# breakout.net
KiCad netlist of a schematic drawn in EAGLE
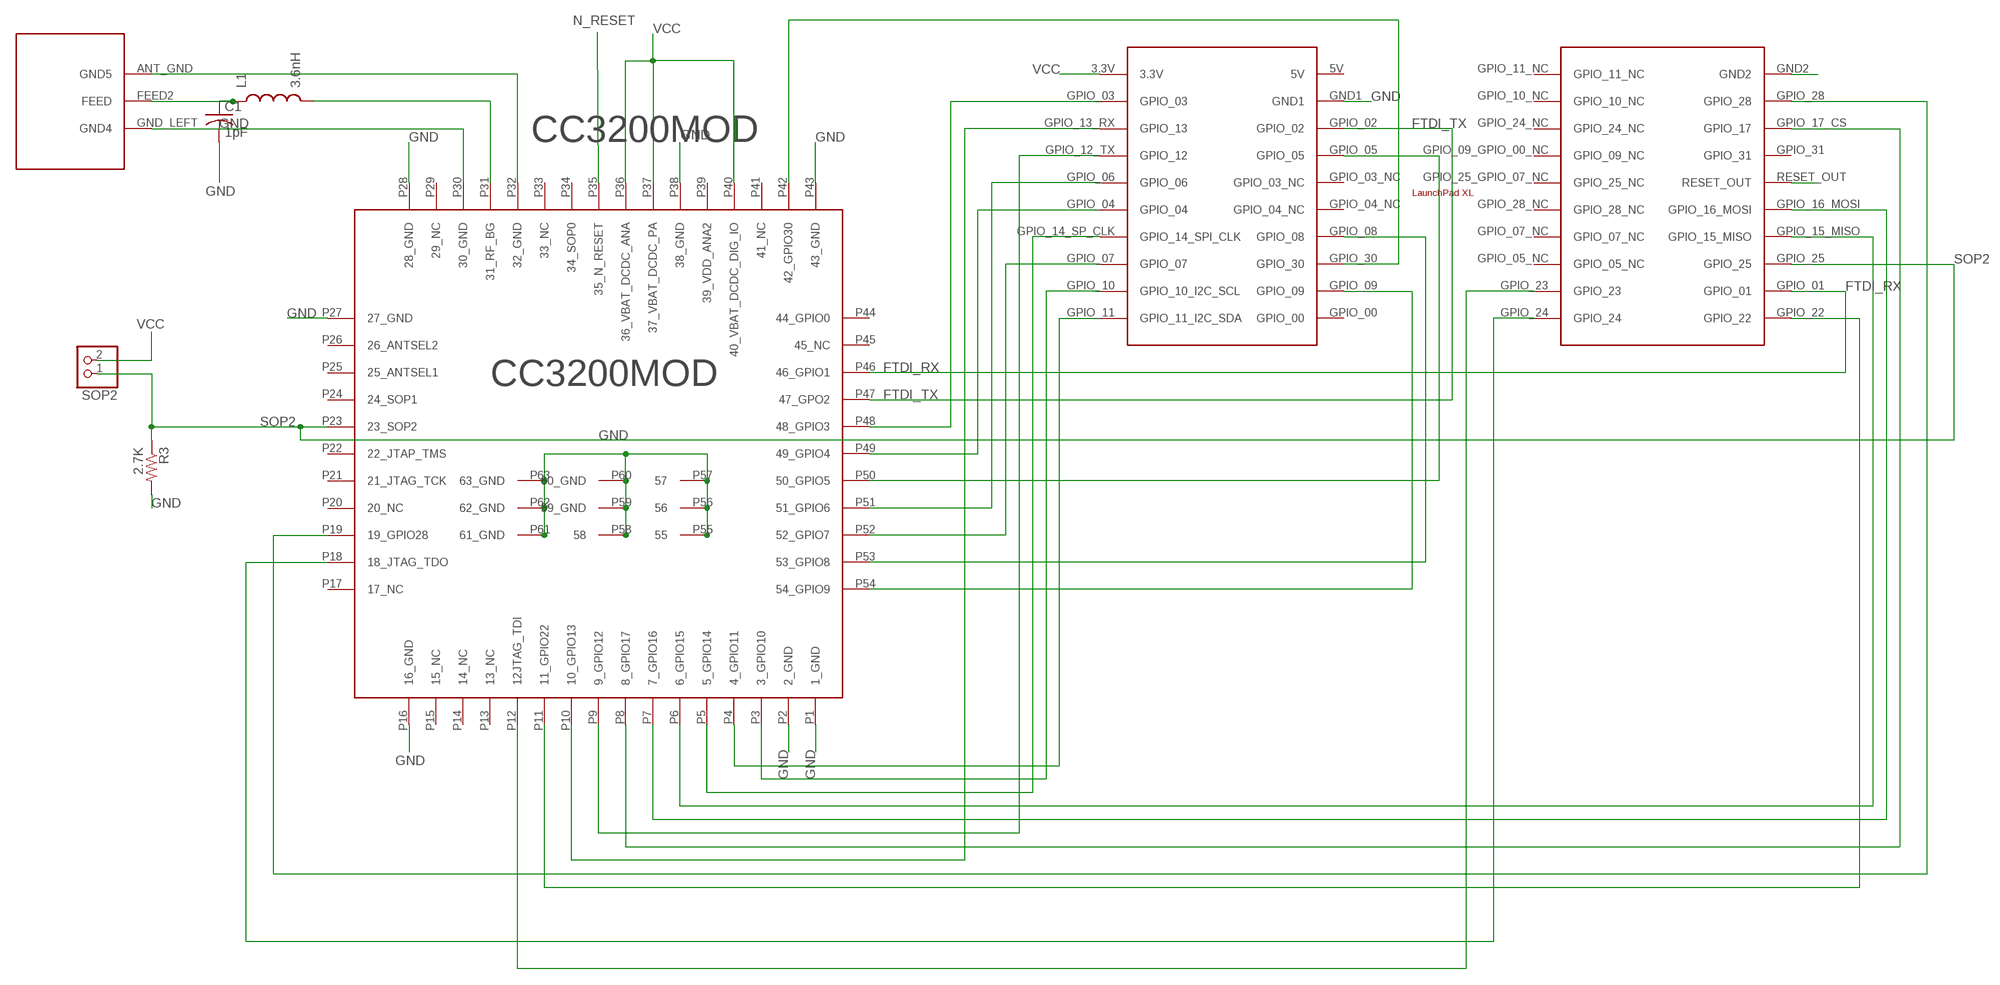
[diagram p0: schematic, sheet 1]
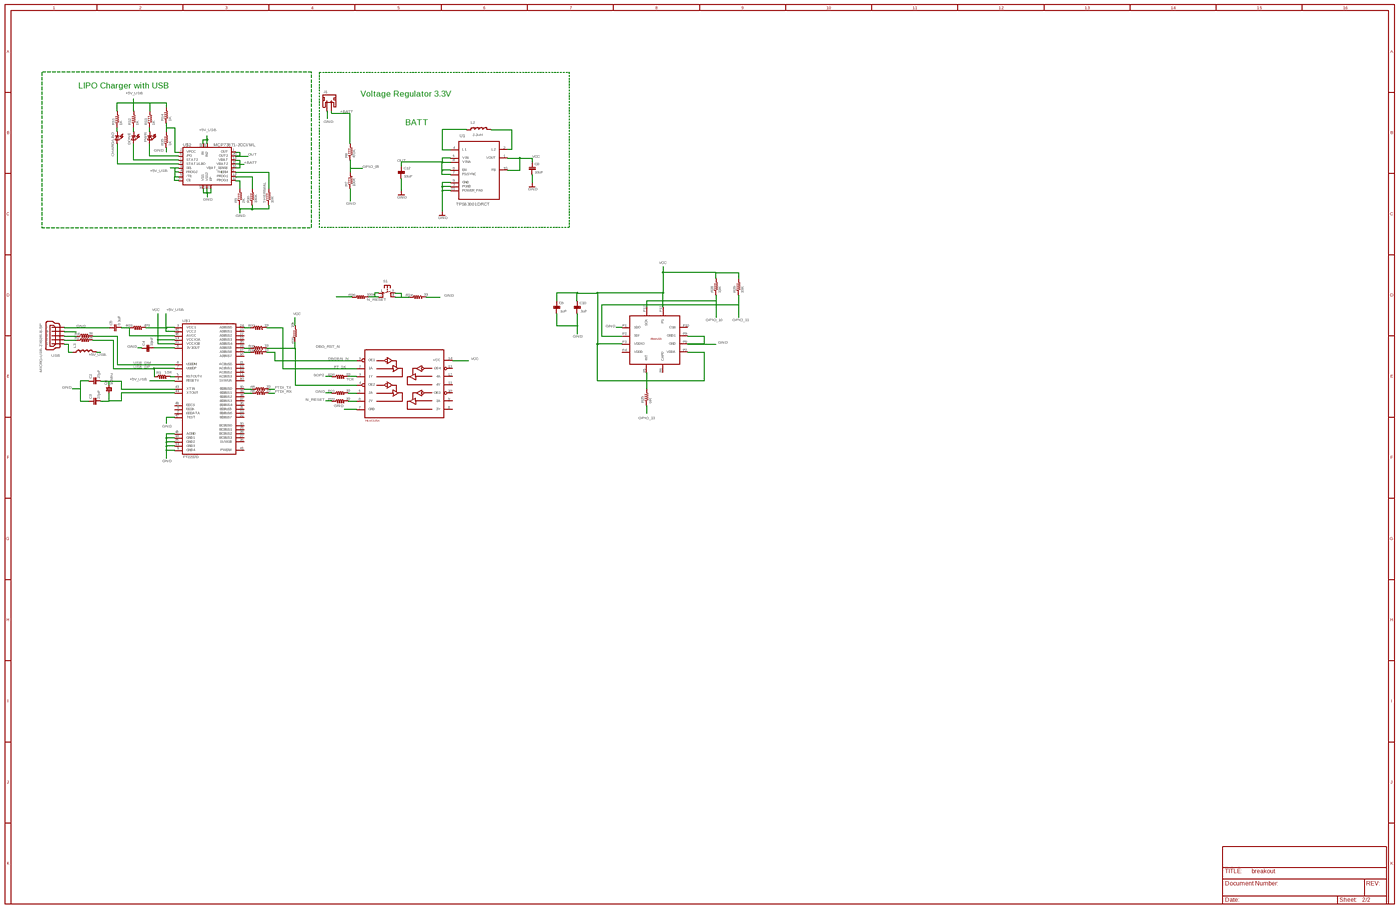
[diagram p1: schematic, sheet 2, overview]
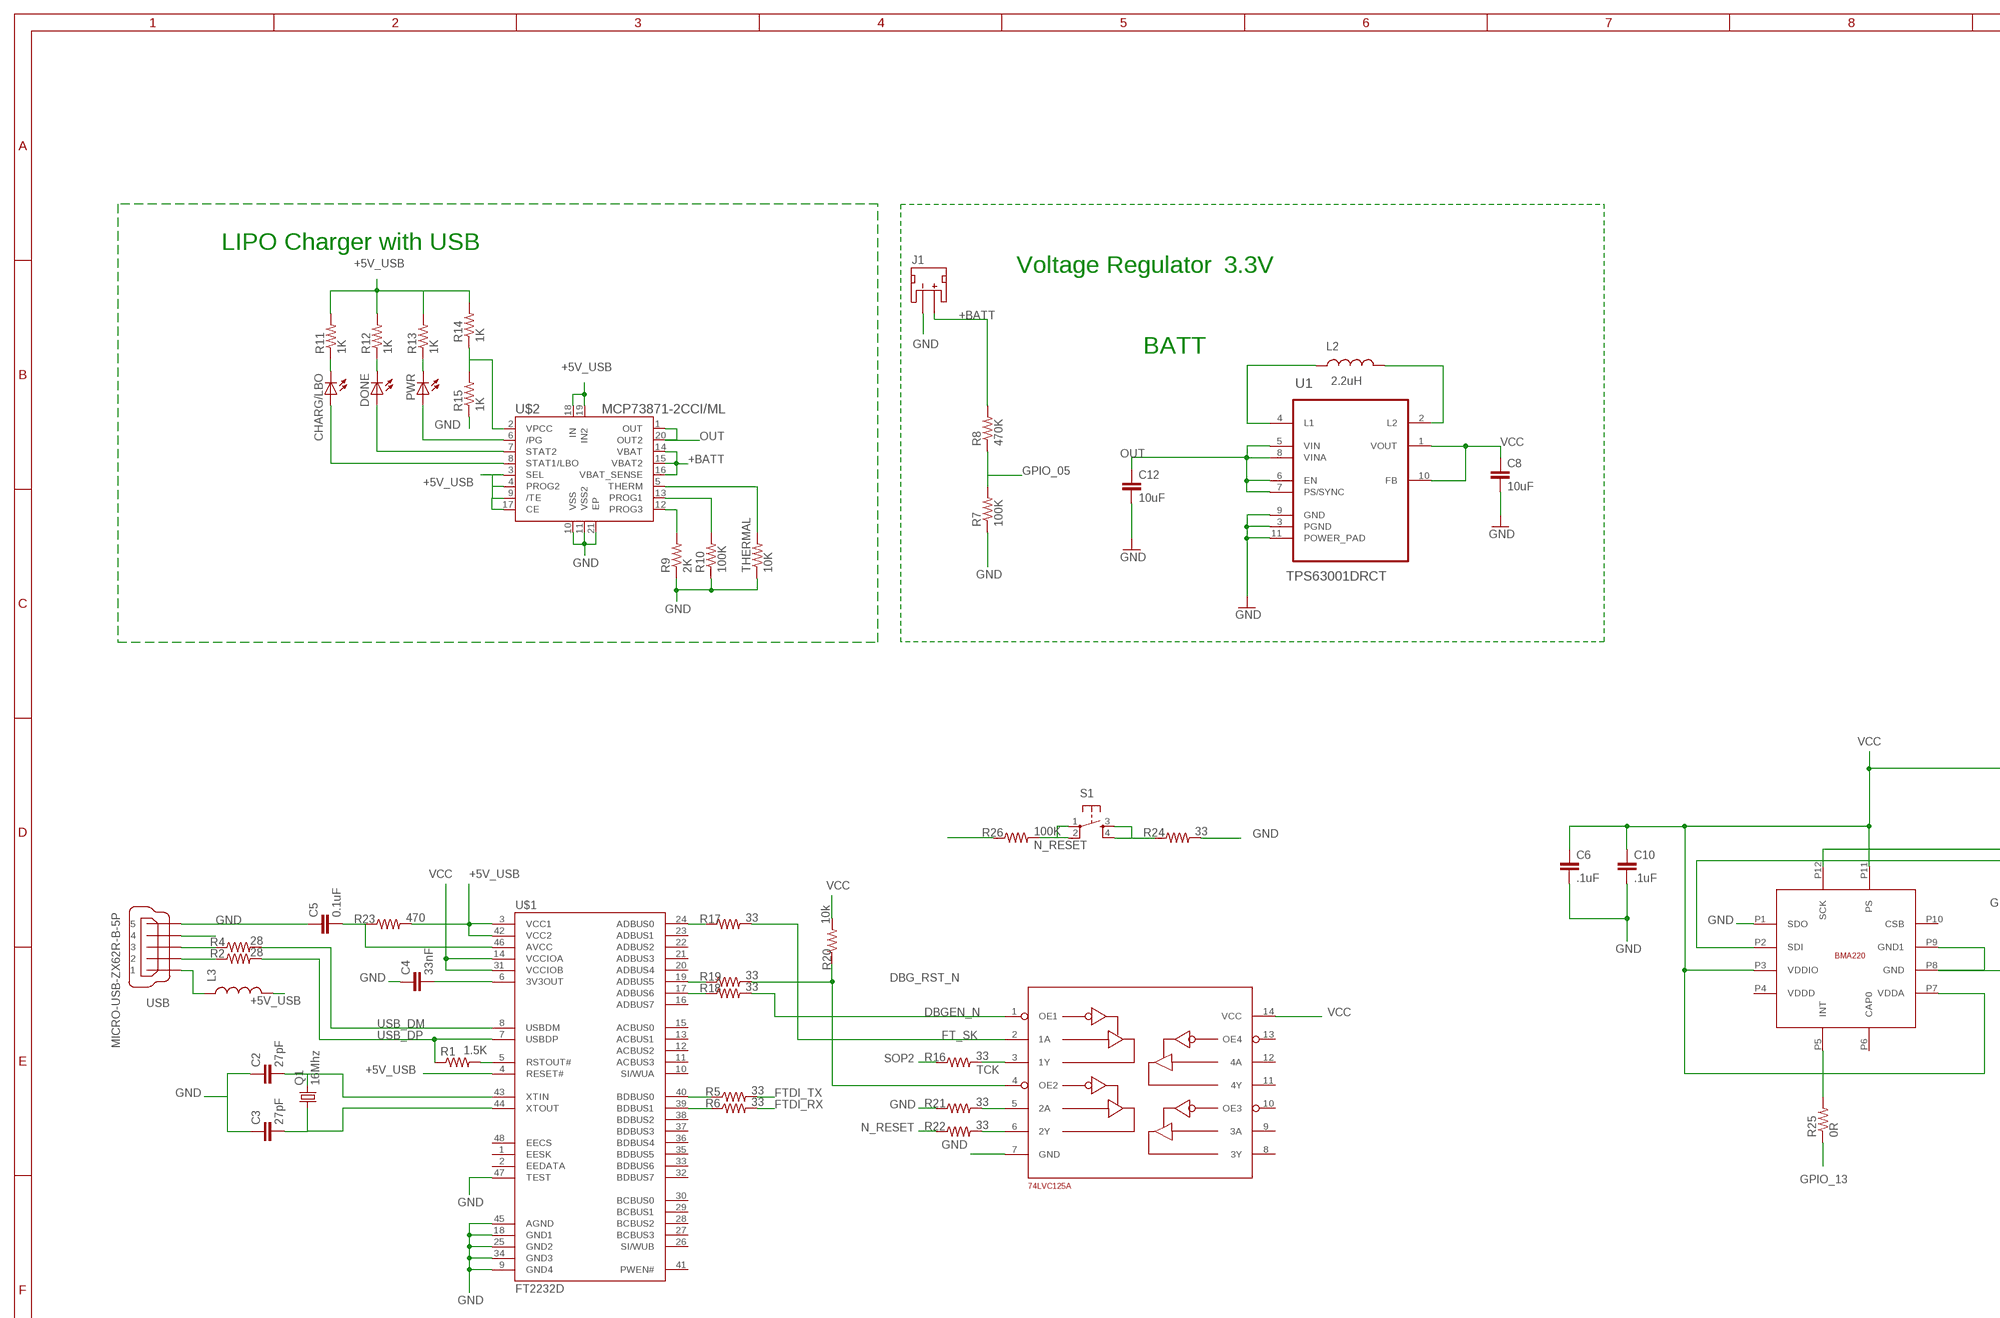
[diagram p2: schematic, sheet 2, part 1 of 4]
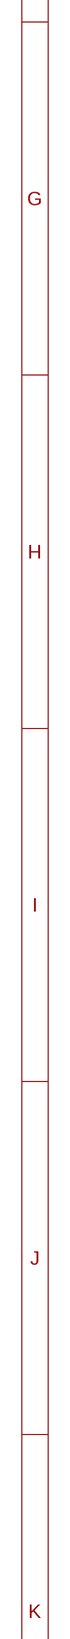
[diagram p3: schematic, sheet 2, part 2 of 4]
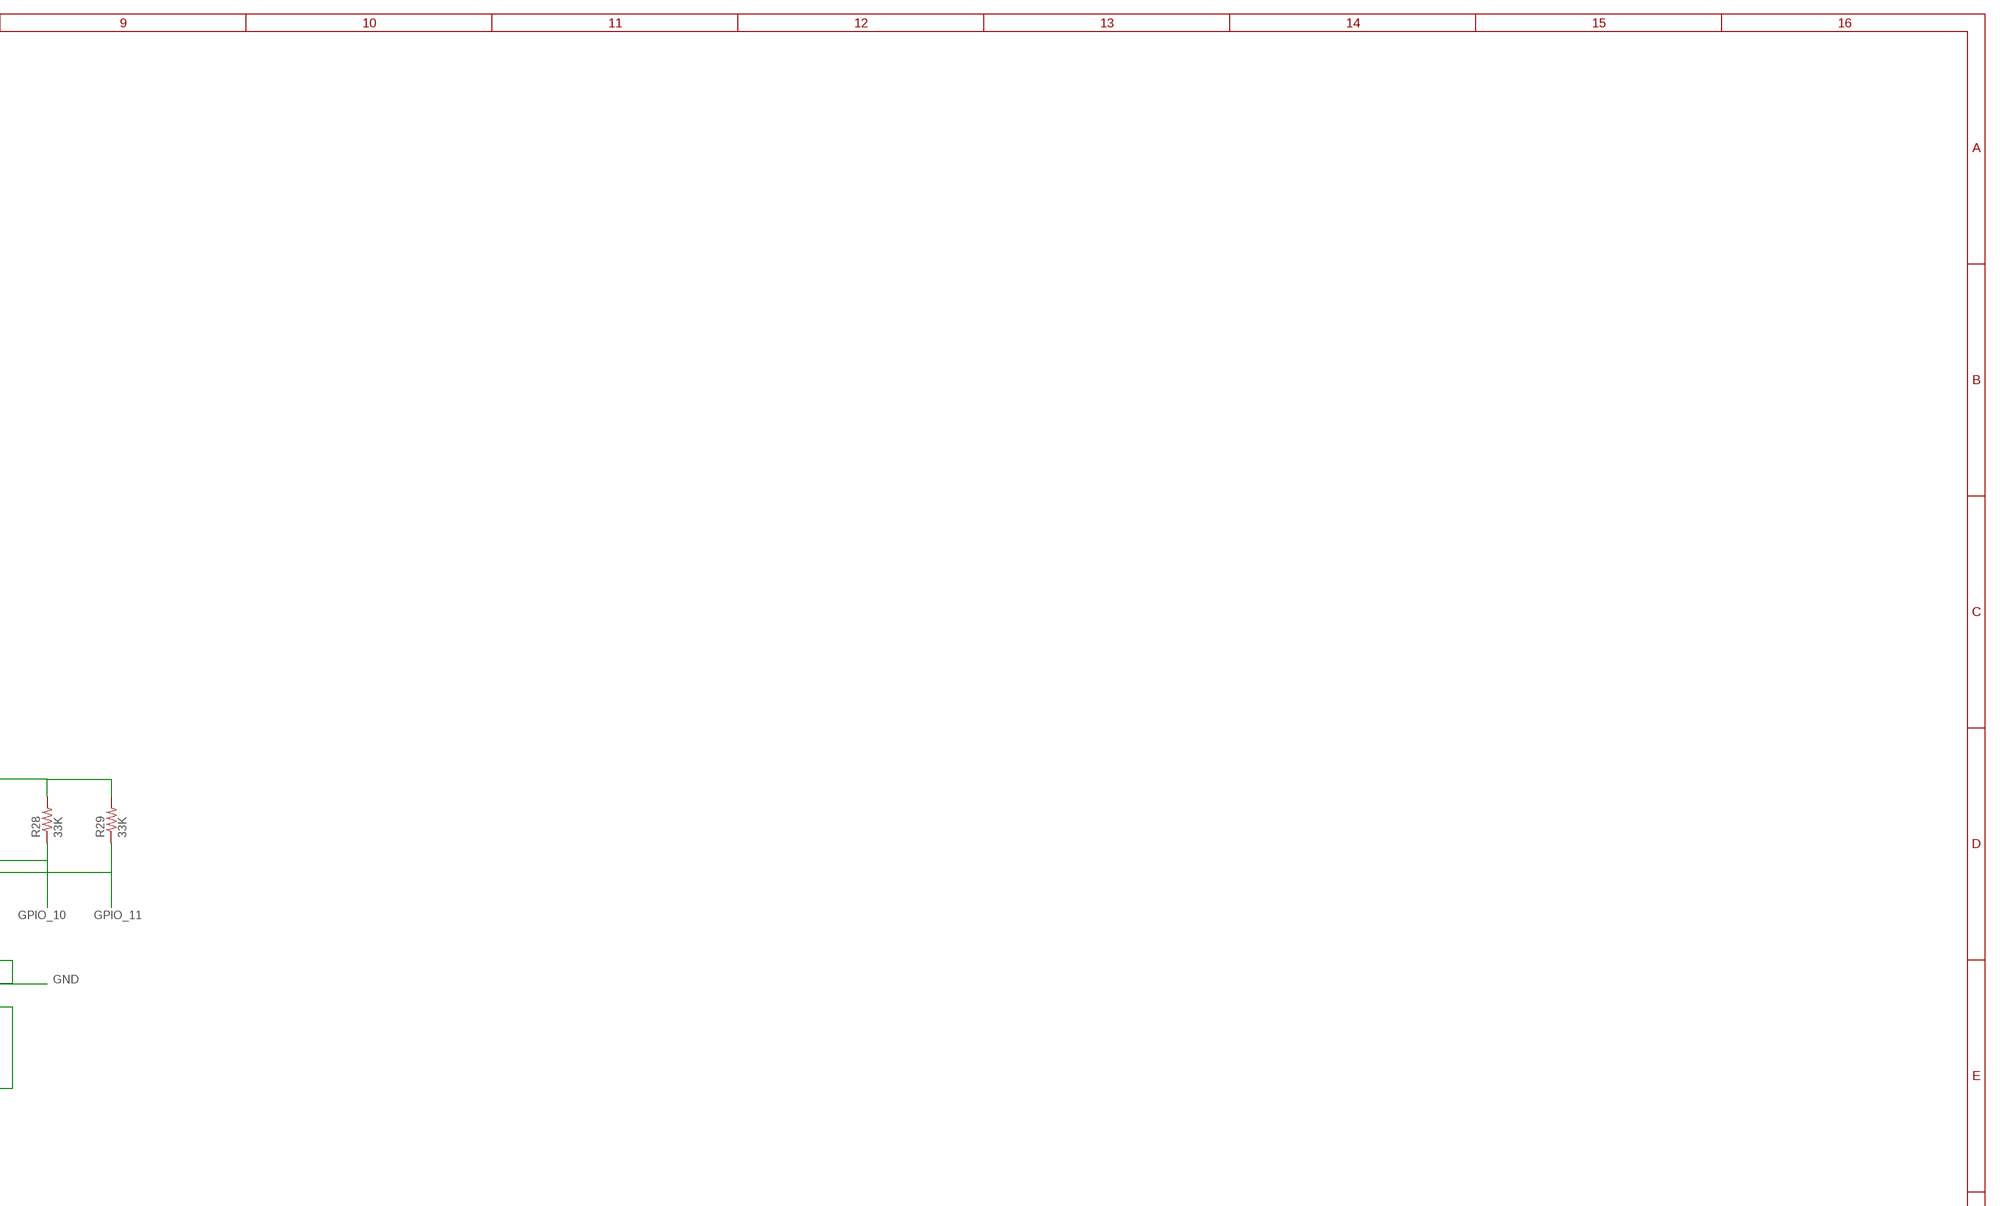
[diagram p4: schematic, sheet 2, part 3 of 4]
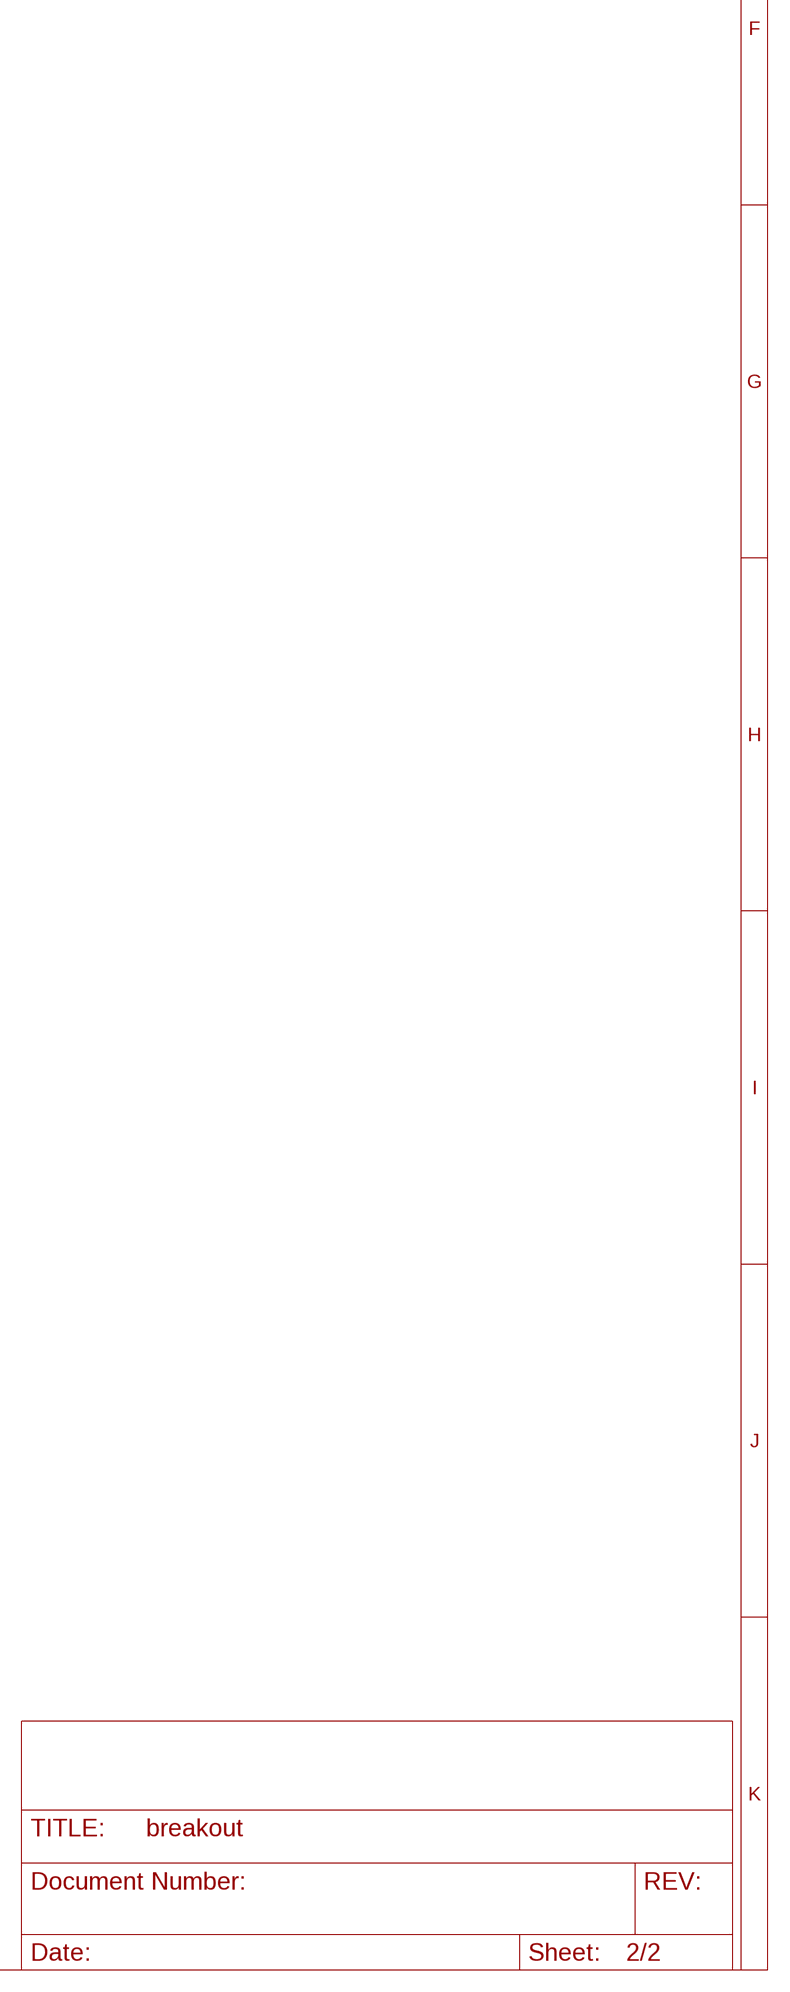
[diagram p5: schematic, sheet 2, part 4 of 4]

(export (version "E")
  (design (tool "Eeschema 10.0.6"))
  (components
    (comp (ref "C2")
      (value "27pF")
      (footprint "eagle-import:0402-CAP")
      (libsource (lib "eagle-import") (part "SparkFun-Passives_CAP0402-CAP"))
    )
    (comp (ref "C3")
      (value "27pF")
      (footprint "eagle-import:0402-CAP")
      (libsource (lib "eagle-import") (part "SparkFun-Passives_CAP0402-CAP"))
    )
    (comp (ref "C4")
      (value "33nF")
      (footprint "eagle-import:0402-CAP")
      (libsource (lib "eagle-import") (part "SparkFun-Passives_CAP0402-CAP"))
    )
    (comp (ref "C5")
      (value "0.1uF")
      (footprint "eagle-import:0402-CAP")
      (libsource (lib "eagle-import") (part "SparkFun-Passives_CAP0402-CAP"))
    )
    (comp (ref "C6")
      (value ".1uF")
      (footprint "eagle-import:0402-CAP")
      (libsource (lib "eagle-import") (part "CAP0402-CAP"))
    )
    (comp (ref "C8")
      (value "10uF")
      (footprint "eagle-import:C0603")
      (libsource (lib "eagle-import") (part "C-EUC0603"))
    )
    (comp (ref "C10")
      (value ".1uF")
      (footprint "eagle-import:0402-CAP")
      (libsource (lib "eagle-import") (part "CAP0402-CAP"))
    )
    (comp (ref "C12")
      (value "10uF")
      (footprint "eagle-import:C0603")
      (libsource (lib "eagle-import") (part "C-EUC0603"))
    )
    (comp (ref "CHARG/LBO")
      (value "LEDSML0603")
      (footprint "eagle-import:SML0603")
      (libsource (lib "eagle-import") (part "LEDSML0603"))
    )
    (comp (ref "DONE")
      (value "LEDSML0603")
      (footprint "eagle-import:SML0603")
      (libsource (lib "eagle-import") (part "LEDSML0603"))
    )
    (comp (ref "J1")
      (value "JST_2MM_MALE")
      (footprint "eagle-import:JST-2-SMD")
      (libsource (lib "eagle-import") (part "JST_2MM_MALE"))
    )
    (comp (ref "L2")
      (value "2.2uH")
      (footprint "eagle-import:0805")
      (libsource (lib "eagle-import") (part "INDUCTOR0805"))
    )
    (comp (ref "L3")
      (value "INDUCTOR-SPARKFUN0603")
      (footprint "eagle-import:0603")
      (libsource (lib "eagle-import") (part "INDUCTOR-SPARKFUN0603"))
    )
    (comp (ref "PWR")
      (value "LEDSML0603")
      (footprint "eagle-import:SML0603")
      (libsource (lib "eagle-import") (part "LEDSML0603"))
    )
    (comp (ref "Q1")
      (value "16Mhz")
      (footprint "eagle-import:TC26H")
      (libsource (lib "eagle-import") (part "CRYSTALTC26H"))
    )
    (comp (ref "R1")
      (value "1.5K")
      (footprint "eagle-import:0603-RES")
      (libsource (lib "eagle-import") (part "RESISTOR0603"))
    )
    (comp (ref "R2")
      (value "28")
      (footprint "eagle-import:0603-RES")
      (libsource (lib "eagle-import") (part "RESISTOR0603-RES"))
    )
    (comp (ref "R4")
      (value "28")
      (footprint "eagle-import:0603-RES")
      (libsource (lib "eagle-import") (part "RESISTOR0603-RES"))
    )
    (comp (ref "R5")
      (value "33")
      (footprint "eagle-import:0603-RES")
      (libsource (lib "eagle-import") (part "RESISTOR0603"))
    )
    (comp (ref "R6")
      (value "33")
      (footprint "eagle-import:0603-RES")
      (libsource (lib "eagle-import") (part "RESISTOR0603"))
    )
    (comp (ref "R7")
      (value "100K")
      (footprint "eagle-import:0603-RES")
      (libsource (lib "eagle-import") (part "RESISTOR0603"))
    )
    (comp (ref "R8")
      (value "470K")
      (footprint "eagle-import:0603-RES")
      (libsource (lib "eagle-import") (part "RESISTOR0603"))
    )
    (comp (ref "R9")
      (value "2K")
      (footprint "eagle-import:0603-RES")
      (libsource (lib "eagle-import") (part "RESISTOR0603-RES"))
    )
    (comp (ref "R10")
      (value "100K")
      (footprint "eagle-import:0603-RES")
      (libsource (lib "eagle-import") (part "RESISTOR0603-RES"))
    )
    (comp (ref "R11")
      (value "1K")
      (footprint "eagle-import:0603-RES")
      (libsource (lib "eagle-import") (part "RESISTOR0603-RES"))
    )
    (comp (ref "R12")
      (value "1K")
      (footprint "eagle-import:0603-RES")
      (libsource (lib "eagle-import") (part "RESISTOR0603-RES"))
    )
    (comp (ref "R13")
      (value "1K")
      (footprint "eagle-import:0603-RES")
      (libsource (lib "eagle-import") (part "RESISTOR0603-RES"))
    )
    (comp (ref "R14")
      (value "1K")
      (footprint "eagle-import:0603-RES")
      (libsource (lib "eagle-import") (part "RESISTOR0603-RES"))
    )
    (comp (ref "R15")
      (value "1K")
      (footprint "eagle-import:0603-RES")
      (libsource (lib "eagle-import") (part "RESISTOR0603-RES"))
    )
    (comp (ref "R16")
      (value "33")
      (footprint "eagle-import:0603-RES")
      (libsource (lib "eagle-import") (part "RESISTOR0603"))
    )
    (comp (ref "R17")
      (value "33")
      (footprint "eagle-import:0603-RES")
      (libsource (lib "eagle-import") (part "RESISTOR0603"))
    )
    (comp (ref "R18")
      (value "33")
      (footprint "eagle-import:0603-RES")
      (libsource (lib "eagle-import") (part "RESISTOR0603"))
    )
    (comp (ref "R19")
      (value "33")
      (footprint "eagle-import:0603-RES")
      (libsource (lib "eagle-import") (part "RESISTOR0603"))
    )
    (comp (ref "R20")
      (value "10k")
      (footprint "eagle-import:0603-RES")
      (libsource (lib "eagle-import") (part "RESISTOR0603"))
    )
    (comp (ref "R21")
      (value "33")
      (footprint "eagle-import:0603-RES")
      (libsource (lib "eagle-import") (part "RESISTOR0603"))
    )
    (comp (ref "R22")
      (value "33")
      (footprint "eagle-import:0603-RES")
      (libsource (lib "eagle-import") (part "RESISTOR0603"))
    )
    (comp (ref "R23")
      (value "470")
      (footprint "eagle-import:0603-RES")
      (libsource (lib "eagle-import") (part "RESISTOR0603"))
    )
    (comp (ref "R24")
      (value "33")
      (footprint "eagle-import:0603-RES")
      (libsource (lib "eagle-import") (part "RESISTOR0603"))
    )
    (comp (ref "R25")
      (value "0R")
      (footprint "eagle-import:0603-RES")
      (libsource (lib "eagle-import") (part "RESISTOR0603-RES"))
    )
    (comp (ref "R26")
      (value "100K")
      (footprint "eagle-import:0603-RES")
      (libsource (lib "eagle-import") (part "RESISTOR0603"))
    )
    (comp (ref "R28")
      (value "33K")
      (footprint "eagle-import:0402-RES")
      (libsource (lib "eagle-import") (part "RESISTOR0402-RES"))
    )
    (comp (ref "R29")
      (value "33K")
      (footprint "eagle-import:0402-RES")
      (libsource (lib "eagle-import") (part "RESISTOR0402-RES"))
    )
    (comp (ref "S1")
      (value "TAC_SWITCHSMD")
      (footprint "eagle-import:TACTILE_SWITCH_SMD")
      (libsource (lib "eagle-import") (part "TAC_SWITCHSMD"))
    )
    (comp (ref "THERMAL")
      (value "10K")
      (footprint "eagle-import:0603-RES")
      (libsource (lib "eagle-import") (part "RESISTOR0603-RES"))
    )
    (comp (ref "U$1")
      (value "FT2232D")
      (footprint "eagle-import:LQFP-48")
      (libsource (lib "eagle-import") (part "FT2232D"))
    )
    (comp (ref "U$2")
      (value "MCP73871-2CCI/ML")
      (footprint "eagle-import:QFN20-4X4")
      (libsource (lib "eagle-import") (part "MCP73871ML-2CCI/"))
    )
    (comp (ref "U$3")
      (value "DECADE-74LVC125A")
      (footprint "eagle-import:DECADE-SO-14")
      (libsource (lib "eagle-import") (part "DECADE-74LVC125A"))
    )
    (comp (ref "U$4")
      (value "BMA220")
      (footprint "eagle-import:BMA222")
      (libsource (lib "eagle-import") (part "BMA220"))
    )
    (comp (ref "U1")
      (value "TPS63001DRCT")
      (footprint "eagle-import:SON50P300X300X100-11N")
      (libsource (lib "eagle-import") (part "TPS63001DRCT"))
    )
    (comp (ref "USB")
      (value "MICRO-USB-ZX62R-B-5P")
      (footprint "eagle-import:ZX62R-B-5P")
      (libsource (lib "eagle-import") (part "MICRO-USB-ZX62R-B-5P"))
    )
    (comp (ref "ANT_PAD")
      (value "ANT")
      (footprint "eagle-import:ANT")
      (libsource (lib "eagle-import") (part "ANT"))
    )
    (comp (ref "C1")
      (value "1pF")
      (footprint "eagle-import:C0402")
      (libsource (lib "eagle-import") (part "C-USC0402"))
    )
    (comp (ref "CC3200MOD")
      (value "CC3200")
      (footprint "eagle-import:CC3200MOD")
      (libsource (lib "eagle-import") (part "CC3200"))
    )
    (comp (ref "L1")
      (value "3.6nH")
      (footprint "eagle-import:C0402")
      (libsource (lib "eagle-import") (part "INDUCTOR-SPARKFUN0402"))
    )
    (comp (ref "R3")
      (value "2.7K")
      (footprint "eagle-import:0603-RES")
      (libsource (lib "eagle-import") (part "RESISTOR0603"))
    )
    (comp (ref "SOP2")
      (value "PINHD-1X2")
      (footprint "eagle-import:1X02")
      (libsource (lib "eagle-import") (part "PINHD-1X2"))
    )
    (comp (ref "U11")
      (value "XL")
      (footprint "eagle-import:LAUNCHPADXL")
      (libsource (lib "eagle-import") (part "XL"))
    )
  )
  (nets
    (net (code "1") (name "+5V_USB") (class "Default")
      (node (ref "L3") (pin "2") (pinfunction "2_2") (pintype "passive"))
      (node (ref "R11") (pin "2") (pinfunction "2_2") (pintype "passive"))
      (node (ref "R12") (pin "2") (pinfunction "2_2") (pintype "passive"))
      (node (ref "R13") (pin "2") (pinfunction "2_2") (pintype "passive"))
      (node (ref "R14") (pin "2") (pinfunction "2_2") (pintype "passive"))
      (node (ref "R23") (pin "2") (pinfunction "2_2") (pintype "passive"))
      (node (ref "U$1") (pin "3") (pinfunction "VCC1_3") (pintype "power_in"))
      (node (ref "U$1") (pin "4") (pinfunction "RESET#_4") (pintype "bidirectional"))
      (node (ref "U$1") (pin "42") (pinfunction "VCC2_42") (pintype "power_in"))
      (node (ref "U$2") (pin "17") (pinfunction "CE_17") (pintype "input"))
      (node (ref "U$2") (pin "18") (pinfunction "IN_18") (pintype "power_in"))
      (node (ref "U$2") (pin "19") (pinfunction "IN2_19") (pintype "power_in"))
      (node (ref "U$2") (pin "3") (pinfunction "SEL_3") (pintype "input"))
      (node (ref "U$2") (pin "4") (pinfunction "PROG2_4") (pintype "input"))
      (node (ref "U$2") (pin "9") (pinfunction "/TE_9") (pintype "input"))
    )
    (net (code "2") (name "+BATT") (class "Default")
      (node (ref "J1") (pin "2") (pinfunction "+_2") (pintype "bidirectional"))
      (node (ref "R8") (pin "2") (pinfunction "2_2") (pintype "passive"))
      (node (ref "U$2") (pin "14") (pinfunction "VBAT_14") (pintype "bidirectional"))
      (node (ref "U$2") (pin "15") (pinfunction "VBAT2_15") (pintype "bidirectional"))
      (node (ref "U$2") (pin "16") (pinfunction "VBAT_SENSE_16") (pintype "bidirectional"))
    )
    (net (code "3") (name "DBGEN_N") (class "Default")
      (node (ref "R18") (pin "2") (pinfunction "2_2") (pintype "passive"))
      (node (ref "U$3") (pin "1") (pinfunction "OE1_1") (pintype "bidirectional"))
    )
    (net (code "4") (name "DBG_RST_N") (class "Default")
      (node (ref "R19") (pin "2") (pinfunction "2_2") (pintype "passive"))
      (node (ref "R20") (pin "1") (pinfunction "1_1") (pintype "passive"))
      (node (ref "U$3") (pin "4") (pinfunction "OE2_4") (pintype "bidirectional"))
    )
    (net (code "5") (name "FTDI_RX") (class "Default")
      (node (ref "CC3200MOD") (pin "P46") (pinfunction "46_GPIO1_P46") (pintype "bidirectional"))
      (node (ref "R6") (pin "2") (pinfunction "2_2") (pintype "passive"))
      (node (ref "U11") (pin "GPIO_01") (pinfunction "GPIO_01_GPIO_01") (pintype "bidirectional"))
    )
    (net (code "6") (name "FTDI_TX") (class "Default")
      (node (ref "CC3200MOD") (pin "P47") (pinfunction "47_GPO2_P47") (pintype "bidirectional"))
      (node (ref "R5") (pin "2") (pinfunction "2_2") (pintype "passive"))
      (node (ref "U11") (pin "GPIO_02") (pinfunction "GPIO_02_GPIO_02") (pintype "bidirectional"))
    )
    (net (code "7") (name "FT_SK") (class "Default")
      (node (ref "R17") (pin "2") (pinfunction "2_2") (pintype "passive"))
      (node (ref "U$3") (pin "2") (pinfunction "1A_2") (pintype "bidirectional"))
    )
    (net (code "8") (name "GND") (class "Default")
      (node (ref "ANT_PAD") (pin "ANT_GND") (pinfunction "GND5_ANT_GND") (pintype "bidirectional"))
      (node (ref "ANT_PAD") (pin "GND_LEFT") (pinfunction "GND4_GND_LEFT") (pintype "bidirectional"))
      (node (ref "C1") (pin "2") (pinfunction "2_2") (pintype "passive"))
      (node (ref "C10") (pin "2") (pinfunction "2_2") (pintype "passive"))
      (node (ref "C12") (pin "2") (pinfunction "2_2") (pintype "passive"))
      (node (ref "C2") (pin "1") (pinfunction "1_1") (pintype "passive"))
      (node (ref "C3") (pin "1") (pinfunction "1_1") (pintype "passive"))
      (node (ref "C4") (pin "1") (pinfunction "1_1") (pintype "passive"))
      (node (ref "C5") (pin "1") (pinfunction "1_1") (pintype "passive"))
      (node (ref "C6") (pin "2") (pinfunction "2_2") (pintype "passive"))
      (node (ref "C8") (pin "2") (pinfunction "2_2") (pintype "passive"))
      (node (ref "CC3200MOD") (pin "P1") (pinfunction "1_GND_P1") (pintype "bidirectional"))
      (node (ref "CC3200MOD") (pin "P16") (pinfunction "16_GND_P16") (pintype "bidirectional"))
      (node (ref "CC3200MOD") (pin "P2") (pinfunction "2_GND_P2") (pintype "bidirectional"))
      (node (ref "CC3200MOD") (pin "P27") (pinfunction "27_GND_P27") (pintype "bidirectional"))
      (node (ref "CC3200MOD") (pin "P28") (pinfunction "28_GND_P28") (pintype "bidirectional"))
      (node (ref "CC3200MOD") (pin "P30") (pinfunction "30_GND_P30") (pintype "bidirectional"))
      (node (ref "CC3200MOD") (pin "P32") (pinfunction "32_GND_P32") (pintype "bidirectional"))
      (node (ref "CC3200MOD") (pin "P38") (pinfunction "38_GND_P38") (pintype "bidirectional"))
      (node (ref "CC3200MOD") (pin "P43") (pinfunction "43_GND_P43") (pintype "bidirectional"))
      (node (ref "CC3200MOD") (pin "P55") (pinfunction "55_P55") (pintype "bidirectional"))
      (node (ref "CC3200MOD") (pin "P56") (pinfunction "56_P56") (pintype "bidirectional"))
      (node (ref "CC3200MOD") (pin "P57") (pinfunction "57_P57") (pintype "bidirectional"))
      (node (ref "CC3200MOD") (pin "P58") (pinfunction "58_P58") (pintype "bidirectional"))
      (node (ref "CC3200MOD") (pin "P59") (pinfunction "59_GND_P59") (pintype "bidirectional"))
      (node (ref "CC3200MOD") (pin "P60") (pinfunction "60_GND_P60") (pintype "bidirectional"))
      (node (ref "CC3200MOD") (pin "P61") (pinfunction "61_GND_P61") (pintype "bidirectional"))
      (node (ref "CC3200MOD") (pin "P62") (pinfunction "62_GND_P62") (pintype "bidirectional"))
      (node (ref "CC3200MOD") (pin "P63") (pinfunction "63_GND_P63") (pintype "bidirectional"))
      (node (ref "J1") (pin "1") (pinfunction "-_1") (pintype "bidirectional"))
      (node (ref "R10") (pin "1") (pinfunction "1_1") (pintype "passive"))
      (node (ref "R15") (pin "1") (pinfunction "1_1") (pintype "passive"))
      (node (ref "R21") (pin "1") (pinfunction "1_1") (pintype "passive"))
      (node (ref "R24") (pin "2") (pinfunction "2_2") (pintype "passive"))
      (node (ref "R3") (pin "2") (pinfunction "2_2") (pintype "passive"))
      (node (ref "R7") (pin "1") (pinfunction "1_1") (pintype "passive"))
      (node (ref "R9") (pin "1") (pinfunction "1_1") (pintype "passive"))
      (node (ref "THERMAL") (pin "1") (pinfunction "1_1") (pintype "passive"))
      (node (ref "U$1") (pin "18") (pinfunction "GND1_18") (pintype "power_in"))
      (node (ref "U$1") (pin "25") (pinfunction "GND2_25") (pintype "power_in"))
      (node (ref "U$1") (pin "34") (pinfunction "GND3_34") (pintype "power_in"))
      (node (ref "U$1") (pin "45") (pinfunction "AGND_45") (pintype "power_in"))
      (node (ref "U$1") (pin "47") (pinfunction "TEST_47") (pintype "input"))
      (node (ref "U$1") (pin "9") (pinfunction "GND4_9") (pintype "bidirectional"))
      (node (ref "U$2") (pin "10") (pinfunction "VSS_10") (pintype "power_in"))
      (node (ref "U$2") (pin "11") (pinfunction "VSS2_11") (pintype "power_in"))
      (node (ref "U$2") (pin "21") (pinfunction "EP_21") (pintype "power_in"))
      (node (ref "U$3") (pin "7") (pinfunction "GND_7") (pintype "bidirectional"))
      (node (ref "U$4") (pin "P1") (pinfunction "SDO_P1") (pintype "bidirectional"))
      (node (ref "U$4") (pin "P8") (pinfunction "GND_P8") (pintype "bidirectional"))
      (node (ref "U$4") (pin "P9") (pinfunction "GND1_P9") (pintype "bidirectional"))
      (node (ref "U1") (pin "11") (pinfunction "POWER_PAD_11") (pintype "passive"))
      (node (ref "U1") (pin "3") (pinfunction "PGND_3") (pintype "passive"))
      (node (ref "U1") (pin "9") (pinfunction "GND_9") (pintype "passive"))
      (node (ref "U11") (pin "GND1") (pinfunction "GND1_GND1") (pintype "bidirectional"))
      (node (ref "U11") (pin "GND2") (pinfunction "GND2_GND2") (pintype "bidirectional"))
      (node (ref "USB") (pin "5") (pinfunction "5_5") (pintype "input"))
    )
    (net (code "9") (name "GPIO_05") (class "Default")
      (node (ref "CC3200MOD") (pin "P50") (pinfunction "50_GPIO5_P50") (pintype "bidirectional"))
      (node (ref "R7") (pin "2") (pinfunction "2_2") (pintype "passive"))
      (node (ref "R8") (pin "1") (pinfunction "1_1") (pintype "passive"))
      (node (ref "U11") (pin "GPIO_05") (pinfunction "GPIO_05_GPIO_05") (pintype "bidirectional"))
    )
    (net (code "10") (name "GPIO_10") (class "Default")
      (node (ref "CC3200MOD") (pin "P3") (pinfunction "3_GPIO10_P3") (pintype "bidirectional"))
      (node (ref "R28") (pin "1") (pinfunction "1_1") (pintype "passive"))
      (node (ref "U$4") (pin "P12") (pinfunction "SCK_P12") (pintype "bidirectional"))
      (node (ref "U11") (pin "GPIO_10") (pinfunction "GPIO_10_I2C_SCL_GPIO_10") (pintype "bidirectional"))
    )
    (net (code "11") (name "GPIO_11") (class "Default")
      (node (ref "CC3200MOD") (pin "P4") (pinfunction "4_GPIO11_P4") (pintype "bidirectional"))
      (node (ref "R29") (pin "1") (pinfunction "1_1") (pintype "passive"))
      (node (ref "U$4") (pin "P2") (pinfunction "SDI_P2") (pintype "bidirectional"))
      (node (ref "U11") (pin "GPIO_11") (pinfunction "GPIO_11_I2C_SDA_GPIO_11") (pintype "bidirectional"))
    )
    (net (code "12") (name "GPIO_13") (class "Default")
      (node (ref "CC3200MOD") (pin "P10") (pinfunction "10_GPIO13_P10") (pintype "bidirectional"))
      (node (ref "R25") (pin "1") (pinfunction "1_1") (pintype "passive"))
      (node (ref "U11") (pin "GPIO_13_RX") (pinfunction "GPIO_13_GPIO_13_RX") (pintype "bidirectional"))
    )
    (net (code "13") (name "N_RESET") (class "Default")
      (node (ref "CC3200MOD") (pin "P35") (pinfunction "35_N_RESET_P35") (pintype "bidirectional"))
      (node (ref "R22") (pin "1") (pinfunction "1_1") (pintype "passive"))
      (node (ref "R26") (pin "2") (pinfunction "2_2") (pintype "passive"))
      (node (ref "S1") (pin "1") (pinfunction "1_1") (pintype "passive"))
      (node (ref "S1") (pin "2") (pinfunction "2_2") (pintype "passive"))
      (node (ref "U11") (pin "RESET_OUT") (pinfunction "RESET_OUT_RESET_OUT") (pintype "bidirectional"))
    )
    (net (code "14") (name "Net-(ANT_PAD-FEED)") (class "Default")
      (node (ref "ANT_PAD") (pin "FEED2") (pinfunction "FEED_FEED2") (pintype "bidirectional"))
      (node (ref "C1") (pin "1") (pinfunction "1_1") (pintype "passive"))
      (node (ref "L1") (pin "1") (pinfunction "1_1") (pintype "passive"))
    )
    (net (code "15") (name "Net-(CC3200MOD-5_GPIO14)") (class "Default")
      (node (ref "CC3200MOD") (pin "P5") (pinfunction "5_GPIO14_P5") (pintype "bidirectional"))
      (node (ref "U11") (pin "GPIO_14_SP_CLK") (pinfunction "GPIO_14_SPI_CLK_GPIO_14_SP_CLK") (pintype "bidirectional"))
    )
    (net (code "16") (name "Net-(CC3200MOD-6_GPIO15)") (class "Default")
      (node (ref "CC3200MOD") (pin "P6") (pinfunction "6_GPIO15_P6") (pintype "bidirectional"))
      (node (ref "U11") (pin "GPIO_15_MISO") (pinfunction "GPIO_15_MISO_GPIO_15_MISO") (pintype "bidirectional"))
    )
    (net (code "17") (name "Net-(CC3200MOD-7_GPIO16)") (class "Default")
      (node (ref "CC3200MOD") (pin "P7") (pinfunction "7_GPIO16_P7") (pintype "bidirectional"))
      (node (ref "U11") (pin "GPIO_16_MOSI") (pinfunction "GPIO_16_MOSI_GPIO_16_MOSI") (pintype "bidirectional"))
    )
    (net (code "18") (name "Net-(CC3200MOD-8_GPIO17)") (class "Default")
      (node (ref "CC3200MOD") (pin "P8") (pinfunction "8_GPIO17_P8") (pintype "bidirectional"))
      (node (ref "U11") (pin "GPIO_17_CS") (pinfunction "GPIO_17_GPIO_17_CS") (pintype "bidirectional"))
    )
    (net (code "19") (name "Net-(CC3200MOD-9_GPIO12)") (class "Default")
      (node (ref "CC3200MOD") (pin "P9") (pinfunction "9_GPIO12_P9") (pintype "bidirectional"))
      (node (ref "U11") (pin "GPIO_12_TX") (pinfunction "GPIO_12_GPIO_12_TX") (pintype "bidirectional"))
    )
    (net (code "20") (name "Net-(CC3200MOD-11_GPIO22)") (class "Default")
      (node (ref "CC3200MOD") (pin "P11") (pinfunction "11_GPIO22_P11") (pintype "bidirectional"))
      (node (ref "U11") (pin "GPIO_22") (pinfunction "GPIO_22_GPIO_22") (pintype "bidirectional"))
    )
    (net (code "21") (name "Net-(CC3200MOD-12JTAG_TDI)") (class "Default")
      (node (ref "CC3200MOD") (pin "P12") (pinfunction "12JTAG_TDI_P12") (pintype "bidirectional"))
      (node (ref "U11") (pin "GPIO_23") (pinfunction "GPIO_23_GPIO_23") (pintype "bidirectional"))
    )
    (net (code "22") (name "Net-(CC3200MOD-18_JTAG_TDO)") (class "Default")
      (node (ref "CC3200MOD") (pin "P18") (pinfunction "18_JTAG_TDO_P18") (pintype "bidirectional"))
      (node (ref "U11") (pin "GPIO_24") (pinfunction "GPIO_24_GPIO_24") (pintype "bidirectional"))
    )
    (net (code "23") (name "Net-(CC3200MOD-19_GPIO28)") (class "Default")
      (node (ref "CC3200MOD") (pin "P19") (pinfunction "19_GPIO28_P19") (pintype "bidirectional"))
      (node (ref "U11") (pin "GPIO_28") (pinfunction "GPIO_28_GPIO_28") (pintype "bidirectional"))
    )
    (net (code "24") (name "Net-(CC3200MOD-31_RF_BG)") (class "Default")
      (node (ref "CC3200MOD") (pin "P31") (pinfunction "31_RF_BG_P31") (pintype "bidirectional"))
      (node (ref "L1") (pin "2") (pinfunction "2_2") (pintype "passive"))
    )
    (net (code "25") (name "Net-(CC3200MOD-42_GPIO30)") (class "Default")
      (node (ref "CC3200MOD") (pin "P42") (pinfunction "42_GPIO30_P42") (pintype "bidirectional"))
      (node (ref "U11") (pin "GPIO_30") (pinfunction "GPIO_30_GPIO_30") (pintype "bidirectional"))
    )
    (net (code "26") (name "Net-(CC3200MOD-48_GPIO3)") (class "Default")
      (node (ref "CC3200MOD") (pin "P48") (pinfunction "48_GPIO3_P48") (pintype "bidirectional"))
      (node (ref "U11") (pin "GPIO_03") (pinfunction "GPIO_03_GPIO_03") (pintype "bidirectional"))
    )
    (net (code "27") (name "Net-(CC3200MOD-49_GPIO4)") (class "Default")
      (node (ref "CC3200MOD") (pin "P49") (pinfunction "49_GPIO4_P49") (pintype "bidirectional"))
      (node (ref "U11") (pin "GPIO_04") (pinfunction "GPIO_04_GPIO_04") (pintype "bidirectional"))
    )
    (net (code "28") (name "Net-(CC3200MOD-51_GPIO6)") (class "Default")
      (node (ref "CC3200MOD") (pin "P51") (pinfunction "51_GPIO6_P51") (pintype "bidirectional"))
      (node (ref "U11") (pin "GPIO_06") (pinfunction "GPIO_06_GPIO_06") (pintype "bidirectional"))
    )
    (net (code "29") (name "Net-(CC3200MOD-52_GPIO7)") (class "Default")
      (node (ref "CC3200MOD") (pin "P52") (pinfunction "52_GPIO7_P52") (pintype "bidirectional"))
      (node (ref "U11") (pin "GPIO_07") (pinfunction "GPIO_07_GPIO_07") (pintype "bidirectional"))
    )
    (net (code "30") (name "Net-(CC3200MOD-53_GPIO8)") (class "Default")
      (node (ref "CC3200MOD") (pin "P53") (pinfunction "53_GPIO8_P53") (pintype "bidirectional"))
      (node (ref "U11") (pin "GPIO_08") (pinfunction "GPIO_08_GPIO_08") (pintype "bidirectional"))
    )
    (net (code "31") (name "Net-(CC3200MOD-54_GPIO9)") (class "Default")
      (node (ref "CC3200MOD") (pin "P54") (pinfunction "54_GPIO9_P54") (pintype "bidirectional"))
      (node (ref "U11") (pin "GPIO_09") (pinfunction "GPIO_09_GPIO_09") (pintype "bidirectional"))
    )
    (net (code "32") (name "Net-(CHARG/LBO-PadC)") (class "Default")
      (node (ref "CHARG/LBO") (pin "C") (pinfunction "C_C") (pintype "passive"))
      (node (ref "R11") (pin "1") (pinfunction "1_1") (pintype "passive"))
    )
    (net (code "33") (name "Net-(DONE-PadC)") (class "Default")
      (node (ref "DONE") (pin "C") (pinfunction "C_C") (pintype "passive"))
      (node (ref "R12") (pin "1") (pinfunction "1_1") (pintype "passive"))
    )
    (net (code "34") (name "Net-(L3-Pad1)") (class "Default")
      (node (ref "L3") (pin "1") (pinfunction "1_1") (pintype "passive"))
      (node (ref "USB") (pin "1") (pinfunction "1_1") (pintype "input"))
    )
    (net (code "35") (name "Net-(PWR-PadC)") (class "Default")
      (node (ref "PWR") (pin "C") (pinfunction "C_C") (pintype "passive"))
      (node (ref "R13") (pin "1") (pinfunction "1_1") (pintype "passive"))
    )
    (net (code "36") (name "Net-(R2-Pad1)") (class "Default")
      (node (ref "R2") (pin "1") (pinfunction "1_1") (pintype "passive"))
      (node (ref "USB") (pin "2") (pinfunction "2_2") (pintype "input"))
    )
    (net (code "37") (name "Net-(R4-Pad1)") (class "Default")
      (node (ref "R4") (pin "1") (pinfunction "1_1") (pintype "passive"))
      (node (ref "USB") (pin "3") (pinfunction "3_3") (pintype "input"))
    )
    (net (code "38") (name "Net-(R24-Pad1)") (class "Default")
      (node (ref "R24") (pin "1") (pinfunction "1_1") (pintype "passive"))
      (node (ref "S1") (pin "3") (pinfunction "3_3") (pintype "passive"))
      (node (ref "S1") (pin "4") (pinfunction "4_4") (pintype "passive"))
    )
    (net (code "39") (name "Net-(U$1-3V3OUT)") (class "Default")
      (node (ref "C4") (pin "2") (pinfunction "2_2") (pintype "passive"))
      (node (ref "U$1") (pin "6") (pinfunction "3V3OUT_6") (pintype "output"))
    )
    (net (code "40") (name "Net-(U$1-ADBUS0)") (class "Default")
      (node (ref "R17") (pin "1") (pinfunction "1_1") (pintype "passive"))
      (node (ref "U$1") (pin "24") (pinfunction "ADBUS0_24") (pintype "bidirectional"))
    )
    (net (code "41") (name "Net-(U$1-ADBUS5)") (class "Default")
      (node (ref "R19") (pin "1") (pinfunction "1_1") (pintype "passive"))
      (node (ref "U$1") (pin "19") (pinfunction "ADBUS5_19") (pintype "bidirectional"))
    )
    (net (code "42") (name "Net-(U$1-ADBUS6)") (class "Default")
      (node (ref "R18") (pin "1") (pinfunction "1_1") (pintype "passive"))
      (node (ref "U$1") (pin "17") (pinfunction "ADBUS6_17") (pintype "bidirectional"))
    )
    (net (code "43") (name "Net-(U$1-AVCC)") (class "Default")
      (node (ref "C5") (pin "2") (pinfunction "2_2") (pintype "passive"))
      (node (ref "R23") (pin "1") (pinfunction "1_1") (pintype "passive"))
      (node (ref "U$1") (pin "46") (pinfunction "AVCC_46") (pintype "bidirectional"))
    )
    (net (code "44") (name "Net-(U$1-BDBUS0)") (class "Default")
      (node (ref "R5") (pin "1") (pinfunction "1_1") (pintype "passive"))
      (node (ref "U$1") (pin "40") (pinfunction "BDBUS0_40") (pintype "output"))
    )
    (net (code "45") (name "Net-(U$1-BDBUS1)") (class "Default")
      (node (ref "R6") (pin "1") (pinfunction "1_1") (pintype "passive"))
      (node (ref "U$1") (pin "39") (pinfunction "BDBUS1_39") (pintype "input"))
    )
    (net (code "46") (name "Net-(U$1-RSTOUT#)") (class "Default")
      (node (ref "R1") (pin "2") (pinfunction "2_2") (pintype "passive"))
      (node (ref "U$1") (pin "5") (pinfunction "RSTOUT#_5") (pintype "bidirectional"))
    )
    (net (code "47") (name "Net-(U$1-XTIN)") (class "Default")
      (node (ref "C2") (pin "2") (pinfunction "2_2") (pintype "passive"))
      (node (ref "Q1") (pin "2") (pinfunction "2_2") (pintype "passive"))
      (node (ref "U$1") (pin "43") (pinfunction "XTIN_43") (pintype "bidirectional"))
    )
    (net (code "48") (name "Net-(U$1-XTOUT)") (class "Default")
      (node (ref "C3") (pin "2") (pinfunction "2_2") (pintype "passive"))
      (node (ref "Q1") (pin "1") (pinfunction "1_1") (pintype "passive"))
      (node (ref "U$1") (pin "44") (pinfunction "XTOUT_44") (pintype "bidirectional"))
    )
    (net (code "49") (name "Net-(U$2-PROG1)") (class "Default")
      (node (ref "R10") (pin "2") (pinfunction "2_2") (pintype "passive"))
      (node (ref "U$2") (pin "13") (pinfunction "PROG1_13") (pintype "bidirectional"))
    )
    (net (code "50") (name "Net-(U$2-PROG3)") (class "Default")
      (node (ref "R9") (pin "2") (pinfunction "2_2") (pintype "passive"))
      (node (ref "U$2") (pin "12") (pinfunction "PROG3_12") (pintype "bidirectional"))
    )
    (net (code "51") (name "Net-(U$2-STAT1{slash}LBO)") (class "Default")
      (node (ref "CHARG/LBO") (pin "A") (pinfunction "A_A") (pintype "passive"))
      (node (ref "U$2") (pin "8") (pinfunction "STAT1/LBO_8") (pintype "open_collector"))
    )
    (net (code "52") (name "Net-(U$2-STAT2)") (class "Default")
      (node (ref "DONE") (pin "A") (pinfunction "A_A") (pintype "passive"))
      (node (ref "U$2") (pin "7") (pinfunction "STAT2_7") (pintype "open_collector"))
    )
    (net (code "53") (name "Net-(U$2-THERM)") (class "Default")
      (node (ref "THERMAL") (pin "2") (pinfunction "2_2") (pintype "passive"))
      (node (ref "U$2") (pin "5") (pinfunction "THERM_5") (pintype "bidirectional"))
    )
    (net (code "54") (name "Net-(U$2-VPCC)") (class "Default")
      (node (ref "R14") (pin "1") (pinfunction "1_1") (pintype "passive"))
      (node (ref "R15") (pin "2") (pinfunction "2_2") (pintype "passive"))
      (node (ref "U$2") (pin "2") (pinfunction "VPCC_2") (pintype "input"))
    )
    (net (code "55") (name "Net-(U$2-{slash}PG)") (class "Default")
      (node (ref "PWR") (pin "A") (pinfunction "A_A") (pintype "passive"))
      (node (ref "U$2") (pin "6") (pinfunction "/PG_6") (pintype "open_collector"))
    )
    (net (code "56") (name "Net-(U$3-2A)") (class "Default")
      (node (ref "R21") (pin "2") (pinfunction "2_2") (pintype "passive"))
      (node (ref "U$3") (pin "5") (pinfunction "2A_5") (pintype "bidirectional"))
    )
    (net (code "57") (name "Net-(U$3-2Y)") (class "Default")
      (node (ref "R22") (pin "2") (pinfunction "2_2") (pintype "passive"))
      (node (ref "U$3") (pin "6") (pinfunction "2Y_6") (pintype "bidirectional"))
    )
    (net (code "58") (name "Net-(U$4-INT)") (class "Default")
      (node (ref "R25") (pin "2") (pinfunction "2_2") (pintype "passive"))
      (node (ref "U$4") (pin "P5") (pinfunction "INT_P5") (pintype "bidirectional"))
    )
    (net (code "59") (name "Net-(U1-L1)") (class "Default")
      (node (ref "L2") (pin "1") (pinfunction "1_1") (pintype "passive"))
      (node (ref "U1") (pin "4") (pinfunction "L1_4") (pintype "passive"))
    )
    (net (code "60") (name "Net-(U1-L2)") (class "Default")
      (node (ref "L2") (pin "2") (pinfunction "2_2") (pintype "passive"))
      (node (ref "U1") (pin "2") (pinfunction "L2_2") (pintype "passive"))
    )
    (net (code "61") (name "OUT") (class "Default")
      (node (ref "C12") (pin "1") (pinfunction "1_1") (pintype "passive"))
      (node (ref "U$2") (pin "1") (pinfunction "OUT_1") (pintype "power_in"))
      (node (ref "U$2") (pin "20") (pinfunction "OUT2_20") (pintype "power_in"))
      (node (ref "U1") (pin "5") (pinfunction "VIN_5") (pintype "power_in"))
      (node (ref "U1") (pin "6") (pinfunction "EN_6") (pintype "input"))
      (node (ref "U1") (pin "7") (pinfunction "PS/SYNC_7") (pintype "input"))
      (node (ref "U1") (pin "8") (pinfunction "VINA_8") (pintype "power_in"))
    )
    (net (code "62") (name "SOP2") (class "Default")
      (node (ref "CC3200MOD") (pin "P23") (pinfunction "23_SOP2_P23") (pintype "bidirectional"))
      (node (ref "R16") (pin "1") (pinfunction "1_1") (pintype "passive"))
      (node (ref "R3") (pin "1") (pinfunction "1_1") (pintype "passive"))
      (node (ref "SOP2") (pin "1") (pinfunction "1_1") (pintype "passive"))
      (node (ref "U11") (pin "GPIO_25") (pinfunction "GPIO_25_GPIO_25") (pintype "bidirectional"))
    )
    (net (code "63") (name "TCK") (class "Default")
      (node (ref "R16") (pin "2") (pinfunction "2_2") (pintype "passive"))
      (node (ref "U$3") (pin "3") (pinfunction "1Y_3") (pintype "bidirectional"))
    )
    (net (code "64") (name "USB_DM") (class "Default")
      (node (ref "R4") (pin "2") (pinfunction "2_2") (pintype "passive"))
      (node (ref "U$1") (pin "8") (pinfunction "USBDM_8") (pintype "bidirectional"))
    )
    (net (code "65") (name "USB_DP") (class "Default")
      (node (ref "R1") (pin "1") (pinfunction "1_1") (pintype "passive"))
      (node (ref "R2") (pin "2") (pinfunction "2_2") (pintype "passive"))
      (node (ref "U$1") (pin "7") (pinfunction "USBDP_7") (pintype "bidirectional"))
    )
    (net (code "66") (name "VCC") (class "Default")
      (node (ref "C10") (pin "1") (pinfunction "1_1") (pintype "passive"))
      (node (ref "C6") (pin "1") (pinfunction "1_1") (pintype "passive"))
      (node (ref "C8") (pin "1") (pinfunction "1_1") (pintype "passive"))
      (node (ref "CC3200MOD") (pin "P36") (pinfunction "36_VBAT_DCDC_ANA_P36") (pintype "bidirectional"))
      (node (ref "CC3200MOD") (pin "P37") (pinfunction "37_VBAT_DCDC_PA_P37") (pintype "bidirectional"))
      (node (ref "CC3200MOD") (pin "P40") (pinfunction "40_VBAT_DCDC_DIG_IO_P40") (pintype "bidirectional"))
      (node (ref "R20") (pin "2") (pinfunction "2_2") (pintype "passive"))
      (node (ref "R26") (pin "1") (pinfunction "1_1") (pintype "passive"))
      (node (ref "R28") (pin "2") (pinfunction "2_2") (pintype "passive"))
      (node (ref "R29") (pin "2") (pinfunction "2_2") (pintype "passive"))
      (node (ref "SOP2") (pin "2") (pinfunction "2_2") (pintype "passive"))
      (node (ref "U$1") (pin "14") (pinfunction "VCCIOA_14") (pintype "power_in"))
      (node (ref "U$1") (pin "31") (pinfunction "VCCIOB_31") (pintype "bidirectional"))
      (node (ref "U$3") (pin "14") (pinfunction "VCC_14") (pintype "bidirectional"))
      (node (ref "U$4") (pin "P11") (pinfunction "PS_P11") (pintype "bidirectional"))
      (node (ref "U$4") (pin "P3") (pinfunction "VDDIO_P3") (pintype "bidirectional"))
      (node (ref "U$4") (pin "P7") (pinfunction "VDDA_P7") (pintype "bidirectional"))
      (node (ref "U1") (pin "1") (pinfunction "VOUT_1") (pintype "output"))
      (node (ref "U1") (pin "10") (pinfunction "FB_10") (pintype "input"))
      (node (ref "U11") (pin "3.3V") (pinfunction "3.3V_3.3V") (pintype "bidirectional"))
    )
    (net (code "67") (name "unconnected-(CC3200MOD-13_NC-PadP13)") (class "Default")
      (node (ref "CC3200MOD") (pin "P13") (pinfunction "13_NC_P13") (pintype "bidirectional"))
    )
    (net (code "68") (name "unconnected-(CC3200MOD-14_NC-PadP14)") (class "Default")
      (node (ref "CC3200MOD") (pin "P14") (pinfunction "14_NC_P14") (pintype "bidirectional"))
    )
    (net (code "69") (name "unconnected-(CC3200MOD-15_NC-PadP15)") (class "Default")
      (node (ref "CC3200MOD") (pin "P15") (pinfunction "15_NC_P15") (pintype "bidirectional"))
    )
    (net (code "70") (name "unconnected-(CC3200MOD-17_NC-PadP17)") (class "Default")
      (node (ref "CC3200MOD") (pin "P17") (pinfunction "17_NC_P17") (pintype "bidirectional"))
    )
    (net (code "71") (name "unconnected-(CC3200MOD-20_NC-PadP20)") (class "Default")
      (node (ref "CC3200MOD") (pin "P20") (pinfunction "20_NC_P20") (pintype "bidirectional"))
    )
    (net (code "72") (name "unconnected-(CC3200MOD-21_JTAG_TCK-PadP21)") (class "Default")
      (node (ref "CC3200MOD") (pin "P21") (pinfunction "21_JTAG_TCK_P21") (pintype "bidirectional"))
    )
    (net (code "73") (name "unconnected-(CC3200MOD-22_JTAP_TMS-PadP22)") (class "Default")
      (node (ref "CC3200MOD") (pin "P22") (pinfunction "22_JTAP_TMS_P22") (pintype "bidirectional"))
    )
    (net (code "74") (name "unconnected-(CC3200MOD-24_SOP1-PadP24)") (class "Default")
      (node (ref "CC3200MOD") (pin "P24") (pinfunction "24_SOP1_P24") (pintype "bidirectional"))
    )
    (net (code "75") (name "unconnected-(CC3200MOD-25_ANTSEL1-PadP25)") (class "Default")
      (node (ref "CC3200MOD") (pin "P25") (pinfunction "25_ANTSEL1_P25") (pintype "bidirectional"))
    )
    (net (code "76") (name "unconnected-(CC3200MOD-26_ANTSEL2-PadP26)") (class "Default")
      (node (ref "CC3200MOD") (pin "P26") (pinfunction "26_ANTSEL2_P26") (pintype "bidirectional"))
    )
    (net (code "77") (name "unconnected-(CC3200MOD-29_NC-PadP29)") (class "Default")
      (node (ref "CC3200MOD") (pin "P29") (pinfunction "29_NC_P29") (pintype "bidirectional"))
    )
    (net (code "78") (name "unconnected-(CC3200MOD-33_NC-PadP33)") (class "Default")
      (node (ref "CC3200MOD") (pin "P33") (pinfunction "33_NC_P33") (pintype "bidirectional"))
    )
    (net (code "79") (name "unconnected-(CC3200MOD-34_SOP0-PadP34)") (class "Default")
      (node (ref "CC3200MOD") (pin "P34") (pinfunction "34_SOP0_P34") (pintype "bidirectional"))
    )
    (net (code "80") (name "unconnected-(CC3200MOD-39_VDD_ANA2-PadP39)") (class "Default")
      (node (ref "CC3200MOD") (pin "P39") (pinfunction "39_VDD_ANA2_P39") (pintype "bidirectional"))
    )
    (net (code "81") (name "unconnected-(CC3200MOD-41_NC-PadP41)") (class "Default")
      (node (ref "CC3200MOD") (pin "P41") (pinfunction "41_NC_P41") (pintype "bidirectional"))
    )
    (net (code "82") (name "unconnected-(CC3200MOD-44_GPIO0-PadP44)") (class "Default")
      (node (ref "CC3200MOD") (pin "P44") (pinfunction "44_GPIO0_P44") (pintype "bidirectional"))
    )
    (net (code "83") (name "unconnected-(CC3200MOD-45_NC-PadP45)") (class "Default")
      (node (ref "CC3200MOD") (pin "P45") (pinfunction "45_NC_P45") (pintype "bidirectional"))
    )
    (net (code "84") (name "unconnected-(J1-PAD1-PadNC1)") (class "Default")
      (node (ref "J1") (pin "NC1") (pinfunction "PAD1_NC1") (pintype "bidirectional"))
    )
    (net (code "85") (name "unconnected-(J1-PAD2-PadNC2)") (class "Default")
      (node (ref "J1") (pin "NC2") (pinfunction "PAD2_NC2") (pintype "bidirectional"))
    )
    (net (code "86") (name "unconnected-(U$1-ACBUS0-Pad15)") (class "Default")
      (node (ref "U$1") (pin "15") (pinfunction "ACBUS0_15") (pintype "bidirectional"))
    )
    (net (code "87") (name "unconnected-(U$1-ACBUS1-Pad13)") (class "Default")
      (node (ref "U$1") (pin "13") (pinfunction "ACBUS1_13") (pintype "bidirectional"))
    )
    (net (code "88") (name "unconnected-(U$1-ACBUS2-Pad12)") (class "Default")
      (node (ref "U$1") (pin "12") (pinfunction "ACBUS2_12") (pintype "bidirectional"))
    )
    (net (code "89") (name "unconnected-(U$1-ACBUS3-Pad11)") (class "Default")
      (node (ref "U$1") (pin "11") (pinfunction "ACBUS3_11") (pintype "bidirectional"))
    )
    (net (code "90") (name "unconnected-(U$1-ADBUS1-Pad23)") (class "Default")
      (node (ref "U$1") (pin "23") (pinfunction "ADBUS1_23") (pintype "bidirectional"))
    )
    (net (code "91") (name "unconnected-(U$1-ADBUS2-Pad22)") (class "Default")
      (node (ref "U$1") (pin "22") (pinfunction "ADBUS2_22") (pintype "bidirectional"))
    )
    (net (code "92") (name "unconnected-(U$1-ADBUS3-Pad21)") (class "Default")
      (node (ref "U$1") (pin "21") (pinfunction "ADBUS3_21") (pintype "bidirectional"))
    )
    (net (code "93") (name "unconnected-(U$1-ADBUS4-Pad20)") (class "Default")
      (node (ref "U$1") (pin "20") (pinfunction "ADBUS4_20") (pintype "bidirectional"))
    )
    (net (code "94") (name "unconnected-(U$1-ADBUS7-Pad16)") (class "Default")
      (node (ref "U$1") (pin "16") (pinfunction "ADBUS7_16") (pintype "bidirectional"))
    )
    (net (code "95") (name "unconnected-(U$1-BCBUS0-Pad30)") (class "Default")
      (node (ref "U$1") (pin "30") (pinfunction "BCBUS0_30") (pintype "bidirectional"))
    )
    (net (code "96") (name "unconnected-(U$1-BCBUS1-Pad29)") (class "Default")
      (node (ref "U$1") (pin "29") (pinfunction "BCBUS1_29") (pintype "bidirectional"))
    )
    (net (code "97") (name "unconnected-(U$1-BCBUS2-Pad28)") (class "Default")
      (node (ref "U$1") (pin "28") (pinfunction "BCBUS2_28") (pintype "bidirectional"))
    )
    (net (code "98") (name "unconnected-(U$1-BCBUS3-Pad27)") (class "Default")
      (node (ref "U$1") (pin "27") (pinfunction "BCBUS3_27") (pintype "bidirectional"))
    )
    (net (code "99") (name "unconnected-(U$1-BDBUS2-Pad38)") (class "Default")
      (node (ref "U$1") (pin "38") (pinfunction "BDBUS2_38") (pintype "output"))
    )
    (net (code "100") (name "unconnected-(U$1-BDBUS3-Pad37)") (class "Default")
      (node (ref "U$1") (pin "37") (pinfunction "BDBUS3_37") (pintype "input"))
    )
    (net (code "101") (name "unconnected-(U$1-BDBUS4-Pad36)") (class "Default")
      (node (ref "U$1") (pin "36") (pinfunction "BDBUS4_36") (pintype "output"))
    )
    (net (code "102") (name "unconnected-(U$1-BDBUS5-Pad35)") (class "Default")
      (node (ref "U$1") (pin "35") (pinfunction "BDBUS5_35") (pintype "input"))
    )
    (net (code "103") (name "unconnected-(U$1-BDBUS6-Pad33)") (class "Default")
      (node (ref "U$1") (pin "33") (pinfunction "BDBUS6_33") (pintype "input"))
    )
    (net (code "104") (name "unconnected-(U$1-BDBUS7-Pad32)") (class "Default")
      (node (ref "U$1") (pin "32") (pinfunction "BDBUS7_32") (pintype "input"))
    )
    (net (code "105") (name "unconnected-(U$1-EECS-Pad48)") (class "Default")
      (node (ref "U$1") (pin "48") (pinfunction "EECS_48") (pintype "bidirectional"))
    )
    (net (code "106") (name "unconnected-(U$1-EEDATA-Pad2)") (class "Default")
      (node (ref "U$1") (pin "2") (pinfunction "EEDATA_2") (pintype "bidirectional"))
    )
    (net (code "107") (name "unconnected-(U$1-EESK-Pad1)") (class "Default")
      (node (ref "U$1") (pin "1") (pinfunction "EESK_1") (pintype "bidirectional"))
    )
    (net (code "108") (name "unconnected-(U$1-PWEN#-Pad41)") (class "Default")
      (node (ref "U$1") (pin "41") (pinfunction "PWEN#_41") (pintype "bidirectional"))
    )
    (net (code "109") (name "unconnected-(U$1-SI{slash}WUA-Pad10)") (class "Default")
      (node (ref "U$1") (pin "10") (pinfunction "SI/WUA_10") (pintype "bidirectional"))
    )
    (net (code "110") (name "unconnected-(U$1-SI{slash}WUB-Pad26)") (class "Default")
      (node (ref "U$1") (pin "26") (pinfunction "SI/WUB_26") (pintype "bidirectional"))
    )
    (net (code "111") (name "unconnected-(U$3-3A-Pad9)") (class "Default")
      (node (ref "U$3") (pin "9") (pinfunction "3A_9") (pintype "bidirectional"))
    )
    (net (code "112") (name "unconnected-(U$3-3Y-Pad8)") (class "Default")
      (node (ref "U$3") (pin "8") (pinfunction "3Y_8") (pintype "bidirectional"))
    )
    (net (code "113") (name "unconnected-(U$3-4A-Pad12)") (class "Default")
      (node (ref "U$3") (pin "12") (pinfunction "4A_12") (pintype "bidirectional"))
    )
    (net (code "114") (name "unconnected-(U$3-4Y-Pad11)") (class "Default")
      (node (ref "U$3") (pin "11") (pinfunction "4Y_11") (pintype "bidirectional"))
    )
    (net (code "115") (name "unconnected-(U$3-OE3-Pad10)") (class "Default")
      (node (ref "U$3") (pin "10") (pinfunction "OE3_10") (pintype "bidirectional"))
    )
    (net (code "116") (name "unconnected-(U$3-OE4-Pad13)") (class "Default")
      (node (ref "U$3") (pin "13") (pinfunction "OE4_13") (pintype "bidirectional"))
    )
    (net (code "117") (name "unconnected-(U$4-CAP0-PadP6)") (class "Default")
      (node (ref "U$4") (pin "P6") (pinfunction "CAP0_P6") (pintype "bidirectional"))
    )
    (net (code "118") (name "unconnected-(U$4-CSB-PadP10)") (class "Default")
      (node (ref "U$4") (pin "P10") (pinfunction "CSB_P10") (pintype "bidirectional"))
    )
    (net (code "119") (name "unconnected-(U$4-VDDD-PadP4)") (class "Default")
      (node (ref "U$4") (pin "P4") (pinfunction "VDDD_P4") (pintype "bidirectional"))
    )
    (net (code "120") (name "unconnected-(U11-GPIO_09_NC-PadGPIO_09_GPIO_00_NC)") (class "Default")
      (node (ref "U11") (pin "GPIO_09_GPIO_00_NC") (pinfunction "GPIO_09_NC_GPIO_09_GPIO_00_NC") (pintype "bidirectional"))
    )
    (net (code "121") (name "unconnected-(U11-GPIO_25_NC-PadGPIO_25_GPIO_07_NC)") (class "Default")
      (node (ref "U11") (pin "GPIO_25_GPIO_07_NC") (pinfunction "GPIO_25_NC_GPIO_25_GPIO_07_NC") (pintype "bidirectional"))
    )
    (net (code "122") (name "unconnected-(U11-Pad5V)") (class "Default")
      (node (ref "U11") (pin "5V") (pinfunction "5V_5V") (pintype "bidirectional"))
    )
    (net (code "123") (name "unconnected-(U11-PadGPIO_00)") (class "Default")
      (node (ref "U11") (pin "GPIO_00") (pinfunction "GPIO_00_GPIO_00") (pintype "bidirectional"))
    )
    (net (code "124") (name "unconnected-(U11-PadGPIO_03_NC)") (class "Default")
      (node (ref "U11") (pin "GPIO_03_NC") (pinfunction "GPIO_03_NC_GPIO_03_NC") (pintype "bidirectional"))
    )
    (net (code "125") (name "unconnected-(U11-PadGPIO_04_NC)") (class "Default")
      (node (ref "U11") (pin "GPIO_04_NC") (pinfunction "GPIO_04_NC_GPIO_04_NC") (pintype "bidirectional"))
    )
    (net (code "126") (name "unconnected-(U11-PadGPIO_05_NC)") (class "Default")
      (node (ref "U11") (pin "GPIO_05_NC") (pinfunction "GPIO_05_NC_GPIO_05_NC") (pintype "bidirectional"))
    )
    (net (code "127") (name "unconnected-(U11-PadGPIO_07_NC)") (class "Default")
      (node (ref "U11") (pin "GPIO_07_NC") (pinfunction "GPIO_07_NC_GPIO_07_NC") (pintype "bidirectional"))
    )
    (net (code "128") (name "unconnected-(U11-PadGPIO_10_NC)") (class "Default")
      (node (ref "U11") (pin "GPIO_10_NC") (pinfunction "GPIO_10_NC_GPIO_10_NC") (pintype "bidirectional"))
    )
    (net (code "129") (name "unconnected-(U11-PadGPIO_11_NC)") (class "Default")
      (node (ref "U11") (pin "GPIO_11_NC") (pinfunction "GPIO_11_NC_GPIO_11_NC") (pintype "bidirectional"))
    )
    (net (code "130") (name "unconnected-(U11-PadGPIO_24_NC)") (class "Default")
      (node (ref "U11") (pin "GPIO_24_NC") (pinfunction "GPIO_24_NC_GPIO_24_NC") (pintype "bidirectional"))
    )
    (net (code "131") (name "unconnected-(U11-PadGPIO_28_NC)") (class "Default")
      (node (ref "U11") (pin "GPIO_28_NC") (pinfunction "GPIO_28_NC_GPIO_28_NC") (pintype "bidirectional"))
    )
    (net (code "132") (name "unconnected-(U11-PadGPIO_31)") (class "Default")
      (node (ref "U11") (pin "GPIO_31") (pinfunction "GPIO_31_GPIO_31") (pintype "bidirectional"))
    )
    (net (code "133") (name "unconnected-(USB-Pad4)") (class "Default")
      (node (ref "USB") (pin "4") (pinfunction "4_4") (pintype "input"))
    )
  )
)
